# MAX1771.net
KiCad netlist of a schematic drawn in Altium Designer
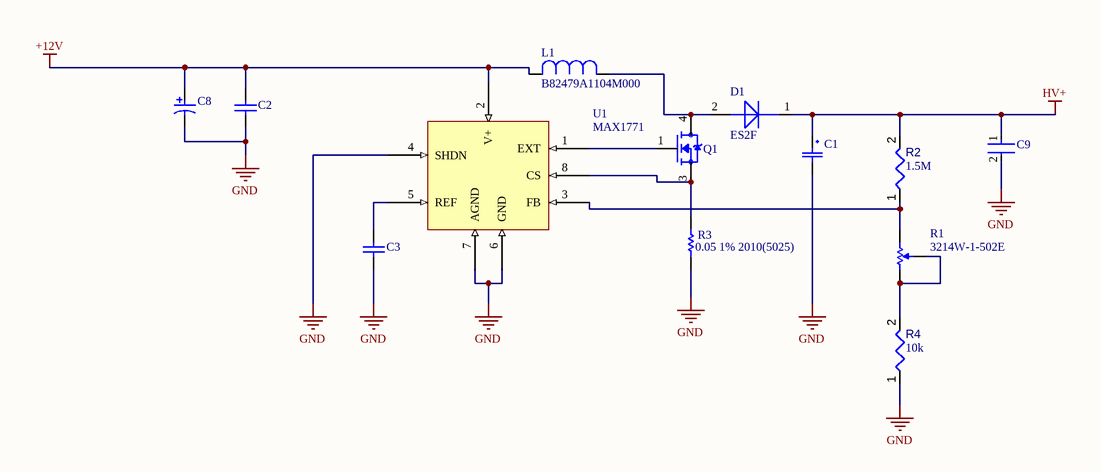
[diagram p0: MAX1771.SchDoc]

(export (version "E")
  (design (tool "Eeschema 10.0.6"))
  (components
    (comp (ref "C1")
      (value "EEV-EB2E100Q")
      (footprint "CAP_UCD_10X10")
      (fields
        (field (name "MANUFACTURER_PART_NUMBER") "UUB2E4R7MNL1GS")
        (field (name "COPYRIGHT") "Copyright (C) 2018 Accelerated Designs. All rights reserved")
      )
      (libsource (lib "HV_LIB") (part "UUB2E4R7MNL1GS"))
    )
    (comp (ref "C2")
      (value "12065C104KAT2A")
      (footprint "CAPC3216X94X50ML20T25")
      (description "Chip Capacitor, Ceramic, 100 nF, 10%, 50 V, 1206, RoHS, Tape and Reel\r\n12065C104KAT2A")
      (fields (field (name "MANUFACTURER") "AVX"))
      (libsource (lib "Altium Content Vault") (part "CAP-NP-2"))
    )
    (comp (ref "C3")
      (value "12065C104KAT2A")
      (footprint "CAPC3216X94X50ML20T25")
      (description "Chip Capacitor, Ceramic, 100 nF, 10%, 50 V, 1206, RoHS, Tape and Reel\r\n12065C104KAT2A")
      (fields (field (name "MANUFACTURER") "AVX"))
      (libsource (lib "Altium Content Vault") (part "CAP-NP-2"))
    )
    (comp (ref "C8")
      (value "TPSD107K010R0100")
      (footprint "AVX-7343-31_L")
      (fields (field (name "TOLERANCE") "±10%") (field (name "MANUFACTURER") "AVX"))
      (libsource (lib "Altium Content Vault") (part "CAP-P-2"))
    )
    (comp (ref "C9")
      (value "C1206C104KARACTU")
      (footprint "FP-C1206C-EB-MFG")
      (description "C1206 0.10 μF X7R 10.00% 250 V")
      (fields (field (name "MANUFACTURER") "KEMET"))
      (libsource (lib "Altium Content Vault") (part "b4654b650e69147ec39a6b967a45e02"))
    )
    (comp (ref "D1")
      (value "ES2F")
      (footprint "DIOM5436X244N - duplicate")
      (libsource (lib "HV_LIB") (part "ES2F_1"))
    )
    (comp (ref "L1")
      (value "B82479A1104M000")
      (footprint "IND_EPCOS_B82479A1")
      (description "No Description Available")
      (fields (field (name "COPYRIGHT") "Copyright (C) 2021 Accelerated Designs. All rights reserved"))
      (libsource (lib "HV_LIB") (part "B82479A1104M000"))
    )
    (comp (ref "Q1")
      (value "IRF740 D2PAK")
      (footprint "D2PAK")
      (libsource (lib "HV_LIB") (part "IRF740 D2PAK"))
    )
    (comp (ref "R1")
      (value "3214W-1-502E")
      (footprint "BOUR-3214W_V")
      (fields (field (name "MANUFACTURER") "Bourns"))
      (libsource (lib "Altium Content Vault") (part "RES-ADJ-3_A"))
    )
    (comp (ref "R2")
      (value "1.5M")
      (footprint "RESC3216X60X45ML15T20")
      (description "Chip Resistor, 1.5M Ohm, +/- 1%, 0.25 W, -55 to 155 degC, 1206 (3216 Metric)")
      (fields (field (name "POWER") "250mW") (field (name "TOLERANCE") "1%"))
      (libsource (lib "University of California Riverside - FSAE") (part "RES-2"))
    )
    (comp (ref "R3")
      (value "0.05 1% 2010(5025)")
      (footprint "RESC2010(5025)_N")
      (description "0.05.75W 1% 2010 (5025 Metric)  SMD\r\n LR2010-R05FW")
      (fields (field (name "TOLERANCE") "1 %") (field (name "POWER") "0.75 W"))
      (libsource (lib "Altium Content Vault") (part "RES"))
    )
    (comp (ref "R4")
      (value "10k")
      (footprint "RESC3216X60X45ML15T20")
      (description "Chip Resistor, 10 KOhm, +/- 1%, 0.25 W, -55 to 155 degC, 1206 (3216 Metric)")
      (fields (field (name "POWER") "250mW") (field (name "TOLERANCE") "1%"))
      (libsource (lib "University of California Riverside - FSAE") (part "RES-2"))
    )
    (comp (ref "U1") (value "MAX1771") (footprint "8-SOIC") (libsource (lib "HV_LIB") (part "MAX1771")))
  )
  (nets
    (net (code "1") (name "+12V") (class "Default")
      (node (ref "C2") (pin "1") (pinfunction "1_1") (pintype "passive"))
      (node (ref "C8") (pin "1") (pinfunction "1_1") (pintype "passive"))
      (node (ref "L1") (pin "2") (pinfunction "2_2") (pintype "passive"))
      (node (ref "U1") (pin "2") (pinfunction "V+_2") (pintype "input"))
    )
    (net (code "2") (name "GND") (class "Default")
      (node (ref "C1") (pin "2") (pinfunction "2_2") (pintype "passive"))
      (node (ref "C2") (pin "2") (pinfunction "2_2") (pintype "passive"))
      (node (ref "C3") (pin "2") (pinfunction "2_2") (pintype "passive"))
      (node (ref "C8") (pin "2") (pinfunction "2_2") (pintype "passive"))
      (node (ref "C9") (pin "2") (pinfunction "2_2") (pintype "passive"))
      (node (ref "R3") (pin "2") (pinfunction "2_2") (pintype "passive"))
      (node (ref "R4") (pin "1") (pinfunction "1_1") (pintype "passive"))
      (node (ref "U1") (pin "4") (pinfunction "SHDN_4") (pintype "input"))
      (node (ref "U1") (pin "6") (pinfunction "GND_6") (pintype "input"))
      (node (ref "U1") (pin "7") (pinfunction "AGND_7") (pintype "input"))
    )
    (net (code "3") (name "HV+") (class "Default")
      (node (ref "C1") (pin "1") (pinfunction "1_1") (pintype "passive"))
      (node (ref "C9") (pin "1") (pinfunction "1_1") (pintype "passive"))
      (node (ref "D1") (pin "1") (pinfunction "1_1") (pintype "passive"))
      (node (ref "R2") (pin "2") (pinfunction "2_2") (pintype "passive"))
    )
    (net (code "4") (name "Net-(Q1-D)") (class "Default")
      (node (ref "D1") (pin "2") (pinfunction "2_2") (pintype "passive"))
      (node (ref "L1") (pin "1") (pinfunction "1_1") (pintype "passive"))
      (node (ref "Q1") (pin "4") (pinfunction "D_4") (pintype "passive"))
    )
    (net (code "5") (name "Net-(Q1-G)") (class "Default")
      (node (ref "Q1") (pin "1") (pinfunction "G_1") (pintype "passive"))
      (node (ref "U1") (pin "1") (pinfunction "EXT_1") (pintype "input"))
    )
    (net (code "6") (name "Net-(Q1-S)") (class "Default")
      (node (ref "Q1") (pin "3") (pinfunction "S_3") (pintype "passive"))
      (node (ref "R3") (pin "1") (pinfunction "1_1") (pintype "passive"))
      (node (ref "U1") (pin "8") (pinfunction "CS_8") (pintype "input"))
    )
    (net (code "7") (name "Net-(R1-Pad1)") (class "Default")
      (node (ref "R1") (pin "1") (pinfunction "1_1") (pintype "passive"))
      (node (ref "R1") (pin "2") (pinfunction "2_2") (pintype "passive"))
      (node (ref "R4") (pin "2") (pinfunction "2_2") (pintype "passive"))
    )
    (net (code "8") (name "Net-(U1-FB)") (class "Default")
      (node (ref "R1") (pin "3") (pinfunction "3_3") (pintype "passive"))
      (node (ref "R2") (pin "1") (pinfunction "1_1") (pintype "passive"))
      (node (ref "U1") (pin "3") (pinfunction "FB_3") (pintype "input"))
    )
    (net (code "9") (name "Net-(U1-REF)") (class "Default")
      (node (ref "C3") (pin "1") (pinfunction "1_1") (pintype "passive"))
      (node (ref "U1") (pin "5") (pinfunction "REF_5") (pintype "input"))
    )
  )
)
